# master.net
KiCad netlist of a schematic drawn in EAGLE
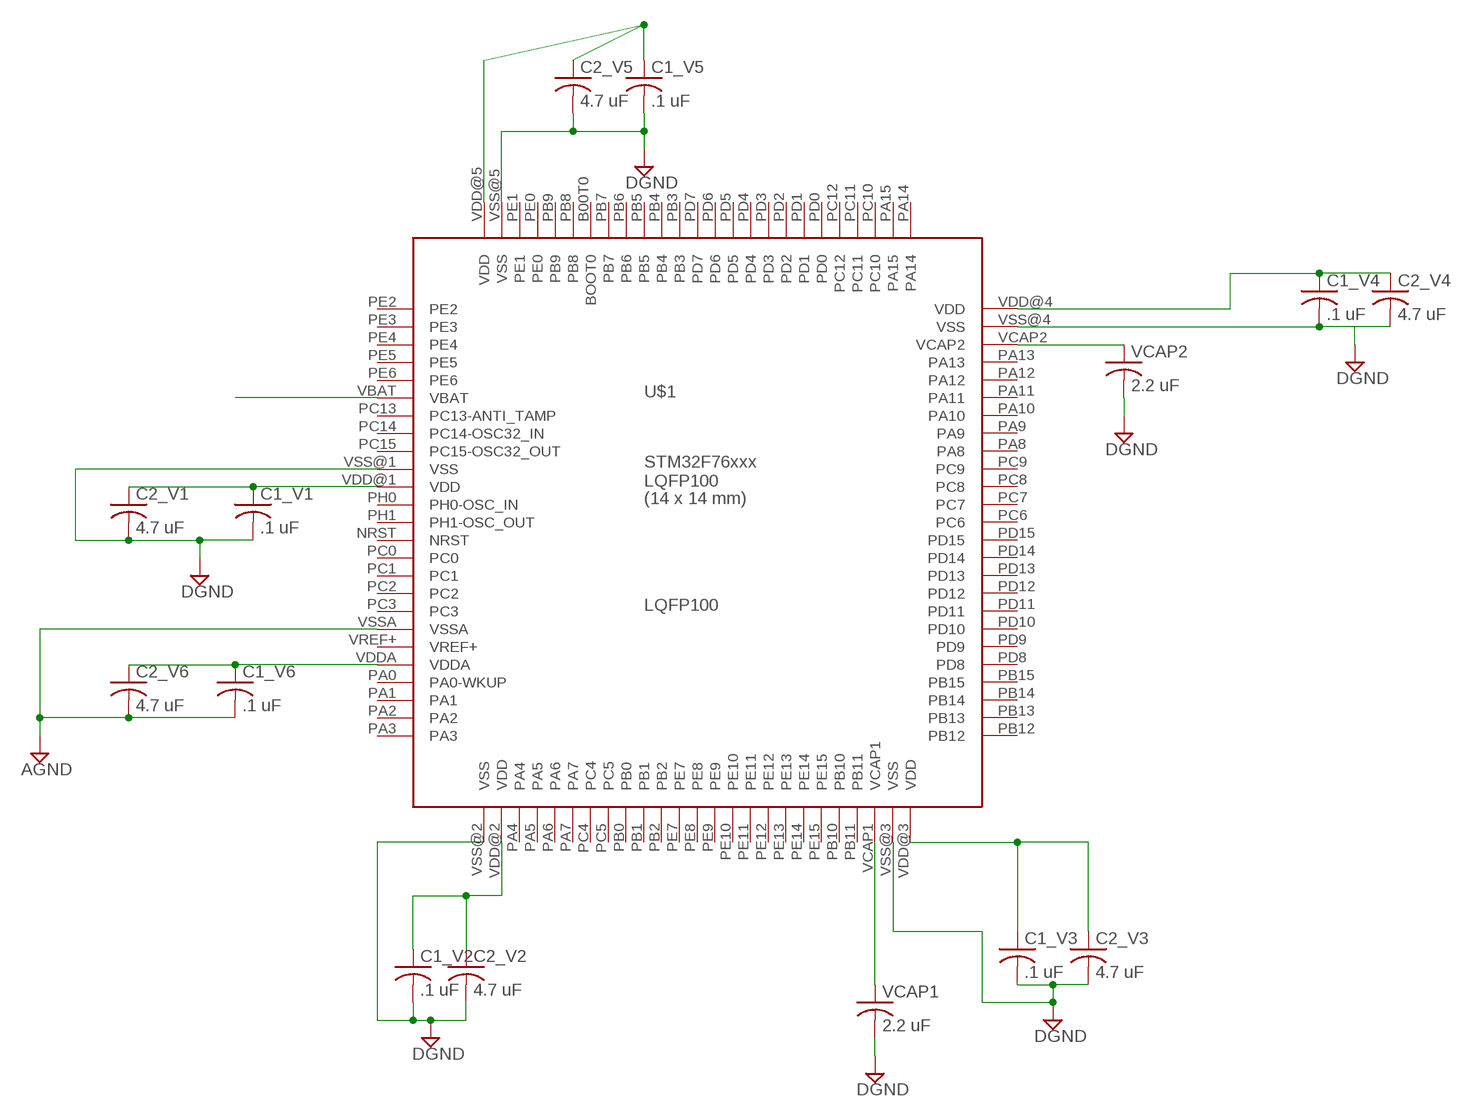
[diagram p0: schematic, sheet 1]
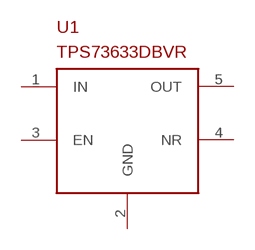
[diagram p1: schematic, sheet 2]

(export (version "E")
  (design (tool "Eeschema 10.0.6"))
  (components
    (comp (ref "C1_V1")
      (value ".1 uF")
      (footprint "eagle-import:C1206")
      (libsource (lib "eagle-import") (part "C-USC1206"))
    )
    (comp (ref "C1_V2")
      (value ".1 uF")
      (footprint "eagle-import:C1206")
      (libsource (lib "eagle-import") (part "C-USC1206"))
    )
    (comp (ref "C1_V3")
      (value ".1 uF")
      (footprint "eagle-import:C1206")
      (libsource (lib "eagle-import") (part "C-USC1206"))
    )
    (comp (ref "C1_V4")
      (value ".1 uF")
      (footprint "eagle-import:C1206")
      (libsource (lib "eagle-import") (part "C-USC1206"))
    )
    (comp (ref "C1_V5")
      (value ".1 uF")
      (footprint "eagle-import:C1206")
      (libsource (lib "eagle-import") (part "C-USC1206"))
    )
    (comp (ref "C1_V6")
      (value ".1 uF")
      (footprint "eagle-import:C1206")
      (libsource (lib "eagle-import") (part "C-USC1206"))
    )
    (comp (ref "C2_V1")
      (value "4.7 uF")
      (footprint "eagle-import:C1206")
      (libsource (lib "eagle-import") (part "C-USC1206"))
    )
    (comp (ref "C2_V2")
      (value "4.7 uF")
      (footprint "eagle-import:C1206")
      (libsource (lib "eagle-import") (part "C-USC1206"))
    )
    (comp (ref "C2_V3")
      (value "4.7 uF")
      (footprint "eagle-import:C1206")
      (libsource (lib "eagle-import") (part "C-USC1206"))
    )
    (comp (ref "C2_V4")
      (value "4.7 uF")
      (footprint "eagle-import:C1206")
      (libsource (lib "eagle-import") (part "C-USC1206"))
    )
    (comp (ref "C2_V5")
      (value "4.7 uF")
      (footprint "eagle-import:C1206")
      (libsource (lib "eagle-import") (part "C-USC1206"))
    )
    (comp (ref "C2_V6")
      (value "4.7 uF")
      (footprint "eagle-import:C1206")
      (libsource (lib "eagle-import") (part "C-USC1206"))
    )
    (comp (ref "U$1")
      (value "LQFP100")
      (footprint "eagle-import:LQFP100")
      (libsource (lib "eagle-import") (part "LQFP100"))
    )
    (comp (ref "VCAP1")
      (value "2.2 uF")
      (footprint "eagle-import:C1206")
      (libsource (lib "eagle-import") (part "C-USC1206"))
    )
    (comp (ref "VCAP2")
      (value "2.2 uF")
      (footprint "eagle-import:C1206")
      (libsource (lib "eagle-import") (part "C-USC1206"))
    )
    (comp (ref "U1")
      (value "TPS73633DBVR")
      (footprint "eagle-import:SOT23-DBV")
      (fields (field (name "MF") "Texas Instruments"))
      (libsource (lib "eagle-import") (part "TPS73633DBVR"))
    )
  )
  (nets
    (net (code "1") (name "AGND") (class "Default")
      (node (ref "C1_V6") (pin "2") (pinfunction "2_2") (pintype "passive"))
      (node (ref "C2_V6") (pin "2") (pinfunction "2_2") (pintype "passive"))
      (node (ref "U$1") (pin "VSSA") (pinfunction "VSSA_VSSA") (pintype "bidirectional"))
    )
    (net (code "2") (name "DGND") (class "Default")
      (node (ref "C1_V1") (pin "2") (pinfunction "2_2") (pintype "passive"))
      (node (ref "C1_V2") (pin "2") (pinfunction "2_2") (pintype "passive"))
      (node (ref "C1_V3") (pin "2") (pinfunction "2_2") (pintype "passive"))
      (node (ref "C1_V5") (pin "2") (pinfunction "2_2") (pintype "passive"))
      (node (ref "C2_V1") (pin "2") (pinfunction "2_2") (pintype "passive"))
      (node (ref "C2_V2") (pin "2") (pinfunction "2_2") (pintype "passive"))
      (node (ref "C2_V3") (pin "2") (pinfunction "2_2") (pintype "passive"))
      (node (ref "C2_V5") (pin "2") (pinfunction "2_2") (pintype "passive"))
      (node (ref "U$1") (pin "VSS@1") (pinfunction "VSS_VSS@1") (pintype "bidirectional"))
      (node (ref "U$1") (pin "VSS@2") (pinfunction "VSS_VSS@2") (pintype "bidirectional"))
      (node (ref "U$1") (pin "VSS@3") (pinfunction "VSS_VSS@3") (pintype "bidirectional"))
      (node (ref "U$1") (pin "VSS@5") (pinfunction "VSS_VSS@5") (pintype "bidirectional"))
      (node (ref "VCAP1") (pin "2") (pinfunction "2_2") (pintype "passive"))
      (node (ref "VCAP2") (pin "2") (pinfunction "2_2") (pintype "passive"))
    )
    (net (code "3") (name "Net-(C1_V1-Pad1)") (class "Default")
      (node (ref "C1_V1") (pin "1") (pinfunction "1_1") (pintype "passive"))
      (node (ref "C2_V1") (pin "1") (pinfunction "1_1") (pintype "passive"))
      (node (ref "U$1") (pin "VDD@1") (pinfunction "VDD_VDD@1") (pintype "bidirectional"))
    )
    (net (code "4") (name "Net-(C1_V2-Pad1)") (class "Default")
      (node (ref "C1_V2") (pin "1") (pinfunction "1_1") (pintype "passive"))
      (node (ref "C2_V2") (pin "1") (pinfunction "1_1") (pintype "passive"))
      (node (ref "U$1") (pin "VDD@2") (pinfunction "VDD_VDD@2") (pintype "bidirectional"))
    )
    (net (code "5") (name "Net-(C1_V3-Pad1)") (class "Default")
      (node (ref "C1_V3") (pin "1") (pinfunction "1_1") (pintype "passive"))
      (node (ref "C2_V3") (pin "1") (pinfunction "1_1") (pintype "passive"))
      (node (ref "U$1") (pin "VDD@3") (pinfunction "VDD_VDD@3") (pintype "bidirectional"))
    )
    (net (code "6") (name "Net-(C1_V4-Pad1)") (class "Default")
      (node (ref "C1_V4") (pin "1") (pinfunction "1_1") (pintype "passive"))
      (node (ref "C2_V4") (pin "1") (pinfunction "1_1") (pintype "passive"))
      (node (ref "U$1") (pin "VDD@4") (pinfunction "VDD_VDD@4") (pintype "bidirectional"))
    )
    (net (code "7") (name "Net-(C1_V4-Pad2)") (class "Default")
      (node (ref "C1_V4") (pin "2") (pinfunction "2_2") (pintype "passive"))
      (node (ref "C2_V4") (pin "2") (pinfunction "2_2") (pintype "passive"))
      (node (ref "U$1") (pin "VSS@4") (pinfunction "VSS_VSS@4") (pintype "bidirectional"))
    )
    (net (code "8") (name "Net-(C1_V5-Pad1)") (class "Default")
      (node (ref "C1_V5") (pin "1") (pinfunction "1_1") (pintype "passive"))
      (node (ref "C2_V5") (pin "1") (pinfunction "1_1") (pintype "passive"))
      (node (ref "U$1") (pin "VDD@5") (pinfunction "VDD_VDD@5") (pintype "bidirectional"))
    )
    (net (code "9") (name "Net-(C1_V6-Pad1)") (class "Default")
      (node (ref "C1_V6") (pin "1") (pinfunction "1_1") (pintype "passive"))
      (node (ref "C2_V6") (pin "1") (pinfunction "1_1") (pintype "passive"))
      (node (ref "U$1") (pin "VDDA") (pinfunction "VDDA_VDDA") (pintype "bidirectional"))
    )
    (net (code "10") (name "Net-(U$1-PadVCAP1)") (class "Default")
      (node (ref "U$1") (pin "VCAP1") (pinfunction "VCAP1_VCAP1") (pintype "bidirectional"))
      (node (ref "VCAP1") (pin "1") (pinfunction "1_1") (pintype "passive"))
    )
    (net (code "11") (name "Net-(U$1-PadVCAP2)") (class "Default")
      (node (ref "U$1") (pin "VCAP2") (pinfunction "VCAP2_VCAP2") (pintype "bidirectional"))
      (node (ref "VCAP2") (pin "1") (pinfunction "1_1") (pintype "passive"))
    )
    (net (code "12") (name "unconnected-(U$1-BOOT0-PadB00T0)") (class "Default")
      (node (ref "U$1") (pin "B00T0") (pinfunction "BOOT0_B00T0") (pintype "bidirectional"))
    )
    (net (code "13") (name "unconnected-(U$1-PA0-WKUP-PadPA0)") (class "Default")
      (node (ref "U$1") (pin "PA0") (pinfunction "PA0-WKUP_PA0") (pintype "bidirectional"))
    )
    (net (code "14") (name "unconnected-(U$1-PC13-ANTI_TAMP-PadPC13)") (class "Default")
      (node (ref "U$1") (pin "PC13") (pinfunction "PC13-ANTI_TAMP_PC13") (pintype "bidirectional"))
    )
    (net (code "15") (name "unconnected-(U$1-PC14-OSC32_IN-PadPC14)") (class "Default")
      (node (ref "U$1") (pin "PC14") (pinfunction "PC14-OSC32_IN_PC14") (pintype "bidirectional"))
    )
    (net (code "16") (name "unconnected-(U$1-PC15-OSC32_OUT-PadPC15)") (class "Default")
      (node (ref "U$1") (pin "PC15") (pinfunction "PC15-OSC32_OUT_PC15") (pintype "bidirectional"))
    )
    (net (code "17") (name "unconnected-(U$1-PH0-OSC_IN-PadPH0)") (class "Default")
      (node (ref "U$1") (pin "PH0") (pinfunction "PH0-OSC_IN_PH0") (pintype "bidirectional"))
    )
    (net (code "18") (name "unconnected-(U$1-PH1-OSC_OUT-PadPH1)") (class "Default")
      (node (ref "U$1") (pin "PH1") (pinfunction "PH1-OSC_OUT_PH1") (pintype "bidirectional"))
    )
    (net (code "19") (name "unconnected-(U$1-PadNRST)") (class "Default")
      (node (ref "U$1") (pin "NRST") (pinfunction "NRST_NRST") (pintype "bidirectional"))
    )
    (net (code "20") (name "unconnected-(U$1-PadPA1)") (class "Default")
      (node (ref "U$1") (pin "PA1") (pinfunction "PA1_PA1") (pintype "bidirectional"))
    )
    (net (code "21") (name "unconnected-(U$1-PadPA2)") (class "Default")
      (node (ref "U$1") (pin "PA2") (pinfunction "PA2_PA2") (pintype "bidirectional"))
    )
    (net (code "22") (name "unconnected-(U$1-PadPA3)") (class "Default")
      (node (ref "U$1") (pin "PA3") (pinfunction "PA3_PA3") (pintype "bidirectional"))
    )
    (net (code "23") (name "unconnected-(U$1-PadPA4)") (class "Default")
      (node (ref "U$1") (pin "PA4") (pinfunction "PA4_PA4") (pintype "bidirectional"))
    )
    (net (code "24") (name "unconnected-(U$1-PadPA5)") (class "Default")
      (node (ref "U$1") (pin "PA5") (pinfunction "PA5_PA5") (pintype "bidirectional"))
    )
    (net (code "25") (name "unconnected-(U$1-PadPA6)") (class "Default")
      (node (ref "U$1") (pin "PA6") (pinfunction "PA6_PA6") (pintype "bidirectional"))
    )
    (net (code "26") (name "unconnected-(U$1-PadPA7)") (class "Default")
      (node (ref "U$1") (pin "PA7") (pinfunction "PA7_PA7") (pintype "bidirectional"))
    )
    (net (code "27") (name "unconnected-(U$1-PadPA8)") (class "Default")
      (node (ref "U$1") (pin "PA8") (pinfunction "PA8_PA8") (pintype "bidirectional"))
    )
    (net (code "28") (name "unconnected-(U$1-PadPA9)") (class "Default")
      (node (ref "U$1") (pin "PA9") (pinfunction "PA9_PA9") (pintype "bidirectional"))
    )
    (net (code "29") (name "unconnected-(U$1-PadPA10)") (class "Default")
      (node (ref "U$1") (pin "PA10") (pinfunction "PA10_PA10") (pintype "bidirectional"))
    )
    (net (code "30") (name "unconnected-(U$1-PadPA11)") (class "Default")
      (node (ref "U$1") (pin "PA11") (pinfunction "PA11_PA11") (pintype "bidirectional"))
    )
    (net (code "31") (name "unconnected-(U$1-PadPA12)") (class "Default")
      (node (ref "U$1") (pin "PA12") (pinfunction "PA12_PA12") (pintype "bidirectional"))
    )
    (net (code "32") (name "unconnected-(U$1-PadPA13)") (class "Default")
      (node (ref "U$1") (pin "PA13") (pinfunction "PA13_PA13") (pintype "bidirectional"))
    )
    (net (code "33") (name "unconnected-(U$1-PadPA14)") (class "Default")
      (node (ref "U$1") (pin "PA14") (pinfunction "PA14_PA14") (pintype "bidirectional"))
    )
    (net (code "34") (name "unconnected-(U$1-PadPA15)") (class "Default")
      (node (ref "U$1") (pin "PA15") (pinfunction "PA15_PA15") (pintype "bidirectional"))
    )
    (net (code "35") (name "unconnected-(U$1-PadPB0)") (class "Default")
      (node (ref "U$1") (pin "PB0") (pinfunction "PB0_PB0") (pintype "bidirectional"))
    )
    (net (code "36") (name "unconnected-(U$1-PadPB1)") (class "Default")
      (node (ref "U$1") (pin "PB1") (pinfunction "PB1_PB1") (pintype "bidirectional"))
    )
    (net (code "37") (name "unconnected-(U$1-PadPB2)") (class "Default")
      (node (ref "U$1") (pin "PB2") (pinfunction "PB2_PB2") (pintype "bidirectional"))
    )
    (net (code "38") (name "unconnected-(U$1-PadPB3)") (class "Default")
      (node (ref "U$1") (pin "PB3") (pinfunction "PB3_PB3") (pintype "bidirectional"))
    )
    (net (code "39") (name "unconnected-(U$1-PadPB4)") (class "Default")
      (node (ref "U$1") (pin "PB4") (pinfunction "PB4_PB4") (pintype "bidirectional"))
    )
    (net (code "40") (name "unconnected-(U$1-PadPB5)") (class "Default")
      (node (ref "U$1") (pin "PB5") (pinfunction "PB5_PB5") (pintype "bidirectional"))
    )
    (net (code "41") (name "unconnected-(U$1-PadPB6)") (class "Default")
      (node (ref "U$1") (pin "PB6") (pinfunction "PB6_PB6") (pintype "bidirectional"))
    )
    (net (code "42") (name "unconnected-(U$1-PadPB7)") (class "Default")
      (node (ref "U$1") (pin "PB7") (pinfunction "PB7_PB7") (pintype "bidirectional"))
    )
    (net (code "43") (name "unconnected-(U$1-PadPB8)") (class "Default")
      (node (ref "U$1") (pin "PB8") (pinfunction "PB8_PB8") (pintype "bidirectional"))
    )
    (net (code "44") (name "unconnected-(U$1-PadPB9)") (class "Default")
      (node (ref "U$1") (pin "PB9") (pinfunction "PB9_PB9") (pintype "bidirectional"))
    )
    (net (code "45") (name "unconnected-(U$1-PadPB10)") (class "Default")
      (node (ref "U$1") (pin "PB10") (pinfunction "PB10_PB10") (pintype "bidirectional"))
    )
    (net (code "46") (name "unconnected-(U$1-PadPB11)") (class "Default")
      (node (ref "U$1") (pin "PB11") (pinfunction "PB11_PB11") (pintype "bidirectional"))
    )
    (net (code "47") (name "unconnected-(U$1-PadPB12)") (class "Default")
      (node (ref "U$1") (pin "PB12") (pinfunction "PB12_PB12") (pintype "bidirectional"))
    )
    (net (code "48") (name "unconnected-(U$1-PadPB13)") (class "Default")
      (node (ref "U$1") (pin "PB13") (pinfunction "PB13_PB13") (pintype "bidirectional"))
    )
    (net (code "49") (name "unconnected-(U$1-PadPB14)") (class "Default")
      (node (ref "U$1") (pin "PB14") (pinfunction "PB14_PB14") (pintype "bidirectional"))
    )
    (net (code "50") (name "unconnected-(U$1-PadPB15)") (class "Default")
      (node (ref "U$1") (pin "PB15") (pinfunction "PB15_PB15") (pintype "bidirectional"))
    )
    (net (code "51") (name "unconnected-(U$1-PadPC0)") (class "Default")
      (node (ref "U$1") (pin "PC0") (pinfunction "PC0_PC0") (pintype "bidirectional"))
    )
    (net (code "52") (name "unconnected-(U$1-PadPC1)") (class "Default")
      (node (ref "U$1") (pin "PC1") (pinfunction "PC1_PC1") (pintype "bidirectional"))
    )
    (net (code "53") (name "unconnected-(U$1-PadPC2)") (class "Default")
      (node (ref "U$1") (pin "PC2") (pinfunction "PC2_PC2") (pintype "bidirectional"))
    )
    (net (code "54") (name "unconnected-(U$1-PadPC3)") (class "Default")
      (node (ref "U$1") (pin "PC3") (pinfunction "PC3_PC3") (pintype "bidirectional"))
    )
    (net (code "55") (name "unconnected-(U$1-PadPC4)") (class "Default")
      (node (ref "U$1") (pin "PC4") (pinfunction "PC4_PC4") (pintype "bidirectional"))
    )
    (net (code "56") (name "unconnected-(U$1-PadPC5)") (class "Default")
      (node (ref "U$1") (pin "PC5") (pinfunction "PC5_PC5") (pintype "bidirectional"))
    )
    (net (code "57") (name "unconnected-(U$1-PadPC6)") (class "Default")
      (node (ref "U$1") (pin "PC6") (pinfunction "PC6_PC6") (pintype "bidirectional"))
    )
    (net (code "58") (name "unconnected-(U$1-PadPC7)") (class "Default")
      (node (ref "U$1") (pin "PC7") (pinfunction "PC7_PC7") (pintype "bidirectional"))
    )
    (net (code "59") (name "unconnected-(U$1-PadPC8)") (class "Default")
      (node (ref "U$1") (pin "PC8") (pinfunction "PC8_PC8") (pintype "bidirectional"))
    )
    (net (code "60") (name "unconnected-(U$1-PadPC9)") (class "Default")
      (node (ref "U$1") (pin "PC9") (pinfunction "PC9_PC9") (pintype "bidirectional"))
    )
    (net (code "61") (name "unconnected-(U$1-PadPC10)") (class "Default")
      (node (ref "U$1") (pin "PC10") (pinfunction "PC10_PC10") (pintype "bidirectional"))
    )
    (net (code "62") (name "unconnected-(U$1-PadPC11)") (class "Default")
      (node (ref "U$1") (pin "PC11") (pinfunction "PC11_PC11") (pintype "bidirectional"))
    )
    (net (code "63") (name "unconnected-(U$1-PadPC12)") (class "Default")
      (node (ref "U$1") (pin "PC12") (pinfunction "PC12_PC12") (pintype "bidirectional"))
    )
    (net (code "64") (name "unconnected-(U$1-PadPD0)") (class "Default")
      (node (ref "U$1") (pin "PD0") (pinfunction "PD0_PD0") (pintype "bidirectional"))
    )
    (net (code "65") (name "unconnected-(U$1-PadPD1)") (class "Default")
      (node (ref "U$1") (pin "PD1") (pinfunction "PD1_PD1") (pintype "bidirectional"))
    )
    (net (code "66") (name "unconnected-(U$1-PadPD2)") (class "Default")
      (node (ref "U$1") (pin "PD2") (pinfunction "PD2_PD2") (pintype "bidirectional"))
    )
    (net (code "67") (name "unconnected-(U$1-PadPD3)") (class "Default")
      (node (ref "U$1") (pin "PD3") (pinfunction "PD3_PD3") (pintype "bidirectional"))
    )
    (net (code "68") (name "unconnected-(U$1-PadPD4)") (class "Default")
      (node (ref "U$1") (pin "PD4") (pinfunction "PD4_PD4") (pintype "bidirectional"))
    )
    (net (code "69") (name "unconnected-(U$1-PadPD5)") (class "Default")
      (node (ref "U$1") (pin "PD5") (pinfunction "PD5_PD5") (pintype "bidirectional"))
    )
    (net (code "70") (name "unconnected-(U$1-PadPD6)") (class "Default")
      (node (ref "U$1") (pin "PD6") (pinfunction "PD6_PD6") (pintype "bidirectional"))
    )
    (net (code "71") (name "unconnected-(U$1-PadPD7)") (class "Default")
      (node (ref "U$1") (pin "PD7") (pinfunction "PD7_PD7") (pintype "bidirectional"))
    )
    (net (code "72") (name "unconnected-(U$1-PadPD8)") (class "Default")
      (node (ref "U$1") (pin "PD8") (pinfunction "PD8_PD8") (pintype "bidirectional"))
    )
    (net (code "73") (name "unconnected-(U$1-PadPD9)") (class "Default")
      (node (ref "U$1") (pin "PD9") (pinfunction "PD9_PD9") (pintype "bidirectional"))
    )
    (net (code "74") (name "unconnected-(U$1-PadPD10)") (class "Default")
      (node (ref "U$1") (pin "PD10") (pinfunction "PD10_PD10") (pintype "bidirectional"))
    )
    (net (code "75") (name "unconnected-(U$1-PadPD11)") (class "Default")
      (node (ref "U$1") (pin "PD11") (pinfunction "PD11_PD11") (pintype "bidirectional"))
    )
    (net (code "76") (name "unconnected-(U$1-PadPD12)") (class "Default")
      (node (ref "U$1") (pin "PD12") (pinfunction "PD12_PD12") (pintype "bidirectional"))
    )
    (net (code "77") (name "unconnected-(U$1-PadPD13)") (class "Default")
      (node (ref "U$1") (pin "PD13") (pinfunction "PD13_PD13") (pintype "bidirectional"))
    )
    (net (code "78") (name "unconnected-(U$1-PadPD14)") (class "Default")
      (node (ref "U$1") (pin "PD14") (pinfunction "PD14_PD14") (pintype "bidirectional"))
    )
    (net (code "79") (name "unconnected-(U$1-PadPD15)") (class "Default")
      (node (ref "U$1") (pin "PD15") (pinfunction "PD15_PD15") (pintype "bidirectional"))
    )
    (net (code "80") (name "unconnected-(U$1-PadPE0)") (class "Default")
      (node (ref "U$1") (pin "PE0") (pinfunction "PE0_PE0") (pintype "bidirectional"))
    )
    (net (code "81") (name "unconnected-(U$1-PadPE1)") (class "Default")
      (node (ref "U$1") (pin "PE1") (pinfunction "PE1_PE1") (pintype "bidirectional"))
    )
    (net (code "82") (name "unconnected-(U$1-PadPE2)") (class "Default")
      (node (ref "U$1") (pin "PE2") (pinfunction "PE2_PE2") (pintype "bidirectional"))
    )
    (net (code "83") (name "unconnected-(U$1-PadPE3)") (class "Default")
      (node (ref "U$1") (pin "PE3") (pinfunction "PE3_PE3") (pintype "bidirectional"))
    )
    (net (code "84") (name "unconnected-(U$1-PadPE4)") (class "Default")
      (node (ref "U$1") (pin "PE4") (pinfunction "PE4_PE4") (pintype "bidirectional"))
    )
    (net (code "85") (name "unconnected-(U$1-PadPE5)") (class "Default")
      (node (ref "U$1") (pin "PE5") (pinfunction "PE5_PE5") (pintype "bidirectional"))
    )
    (net (code "86") (name "unconnected-(U$1-PadPE6)") (class "Default")
      (node (ref "U$1") (pin "PE6") (pinfunction "PE6_PE6") (pintype "bidirectional"))
    )
    (net (code "87") (name "unconnected-(U$1-PadPE7)") (class "Default")
      (node (ref "U$1") (pin "PE7") (pinfunction "PE7_PE7") (pintype "bidirectional"))
    )
    (net (code "88") (name "unconnected-(U$1-PadPE8)") (class "Default")
      (node (ref "U$1") (pin "PE8") (pinfunction "PE8_PE8") (pintype "bidirectional"))
    )
    (net (code "89") (name "unconnected-(U$1-PadPE9)") (class "Default")
      (node (ref "U$1") (pin "PE9") (pinfunction "PE9_PE9") (pintype "bidirectional"))
    )
    (net (code "90") (name "unconnected-(U$1-PadPE10)") (class "Default")
      (node (ref "U$1") (pin "PE10") (pinfunction "PE10_PE10") (pintype "bidirectional"))
    )
    (net (code "91") (name "unconnected-(U$1-PadPE11)") (class "Default")
      (node (ref "U$1") (pin "PE11") (pinfunction "PE11_PE11") (pintype "bidirectional"))
    )
    (net (code "92") (name "unconnected-(U$1-PadPE12)") (class "Default")
      (node (ref "U$1") (pin "PE12") (pinfunction "PE12_PE12") (pintype "bidirectional"))
    )
    (net (code "93") (name "unconnected-(U$1-PadPE13)") (class "Default")
      (node (ref "U$1") (pin "PE13") (pinfunction "PE13_PE13") (pintype "bidirectional"))
    )
    (net (code "94") (name "unconnected-(U$1-PadPE14)") (class "Default")
      (node (ref "U$1") (pin "PE14") (pinfunction "PE14_PE14") (pintype "bidirectional"))
    )
    (net (code "95") (name "unconnected-(U$1-PadPE15)") (class "Default")
      (node (ref "U$1") (pin "PE15") (pinfunction "PE15_PE15") (pintype "bidirectional"))
    )
    (net (code "96") (name "unconnected-(U$1-PadVBAT)") (class "Default")
      (node (ref "U$1") (pin "VBAT") (pinfunction "VBAT_VBAT") (pintype "bidirectional"))
    )
    (net (code "97") (name "unconnected-(U$1-PadVREF+)") (class "Default")
      (node (ref "U$1") (pin "VREF+") (pinfunction "VREF+_VREF+") (pintype "bidirectional"))
    )
    (net (code "98") (name "unconnected-(U1-EN-Pad3)") (class "Default")
      (node (ref "U1") (pin "3") (pinfunction "EN_3") (pintype "bidirectional"))
    )
    (net (code "99") (name "unconnected-(U1-GND-Pad2)") (class "Default")
      (node (ref "U1") (pin "2") (pinfunction "GND_2") (pintype "bidirectional"))
    )
    (net (code "100") (name "unconnected-(U1-IN-Pad1)") (class "Default")
      (node (ref "U1") (pin "1") (pinfunction "IN_1") (pintype "bidirectional"))
    )
    (net (code "101") (name "unconnected-(U1-NR-Pad4)") (class "Default")
      (node (ref "U1") (pin "4") (pinfunction "NR_4") (pintype "bidirectional"))
    )
    (net (code "102") (name "unconnected-(U1-OUT-Pad5)") (class "Default")
      (node (ref "U1") (pin "5") (pinfunction "OUT_5") (pintype "bidirectional"))
    )
  )
)
